# Sheet1.net
KiCad netlist of a schematic drawn in Altium Designer
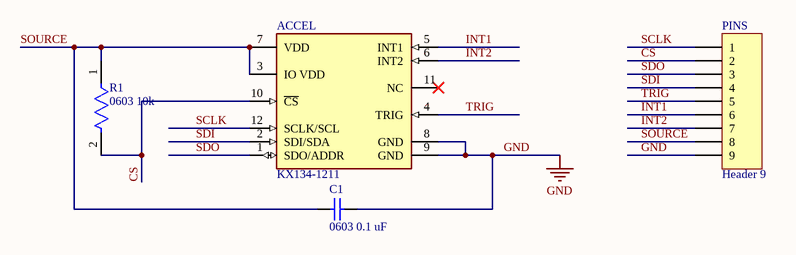
[diagram p0: Sheet1.SchDoc]

(export (version "E")
  (design (tool "Eeschema 10.0.6"))
  (components
    (comp (ref "ACCEL")
      (value "KX134-1211")
      (footprint "FP-KX134-1211-MFG")
      (description "105C OPERATING HIGHER BANDWIDTH,")
      (libsource (lib "Altium Content Vault") (part "690d2a4d51cffb5fe50aad75ddab18e"))
    )
    (comp (ref "C1")
      (value "0603 0.1 uF")
      (footprint "CAPC1608X95X40NL15T15")
      (fields (field (name "PART NUMBER") "VJ0603A101KXBCW1BC") (field (name "MANUFACTURER") "Vitramon"))
      (libsource (lib "Altium Content Vault") (part "CAP"))
    )
    (comp (ref "PINS")
      (value "Header 9")
      (footprint "HDR1X9")
      (description "Header, 9-Pin")
      (fields (field (name "PUBLISHER") "Altium Limited"))
      (libsource (lib "Miscellaneous Connectors") (part "Header 9"))
    )
    (comp (ref "R1")
      (value "0603 10k")
      (footprint "FP-CRCW0603-e3-IPC_C")
      (description "RES Thick Film, 100Ω, 5%, 0.1W, 200ppm/°C, 0603")
      (fields (field (name "TOLERANCE") "5%"))
      (libsource (lib "Altium Content Vault") (part "1029c3af85768c4190bb7ad29bc67b5"))
    )
  )
  (nets
    (net (code "1") (name "/CS") (class "Default")
      (node (ref "ACCEL") (pin "10") (pinfunction "~{CS}_10") (pintype "input"))
      (node (ref "PINS") (pin "2") (pinfunction "2_2") (pintype "passive"))
      (node (ref "R1") (pin "2") (pinfunction "2_2") (pintype "passive"))
    )
    (net (code "2") (name "/INT1") (class "Default")
      (node (ref "ACCEL") (pin "5") (pinfunction "INT1_5") (pintype "input"))
      (node (ref "PINS") (pin "6") (pinfunction "6_6") (pintype "passive"))
    )
    (net (code "3") (name "/INT2") (class "Default")
      (node (ref "ACCEL") (pin "6") (pinfunction "INT2_6") (pintype "input"))
      (node (ref "PINS") (pin "7") (pinfunction "7_7") (pintype "passive"))
    )
    (net (code "4") (name "/SCLK") (class "Default")
      (node (ref "ACCEL") (pin "12") (pinfunction "SCLK/SCL_12") (pintype "input"))
      (node (ref "PINS") (pin "1") (pinfunction "1_1") (pintype "passive"))
    )
    (net (code "5") (name "/SDI") (class "Default")
      (node (ref "ACCEL") (pin "2") (pinfunction "SDI/SDA_2") (pintype "input"))
      (node (ref "PINS") (pin "4") (pinfunction "4_4") (pintype "passive"))
    )
    (net (code "6") (name "/SDO") (class "Default")
      (node (ref "ACCEL") (pin "1") (pinfunction "SDO/ADDR_1") (pintype "bidirectional"))
      (node (ref "PINS") (pin "3") (pinfunction "3_3") (pintype "passive"))
    )
    (net (code "7") (name "/SOURCE") (class "Default")
      (node (ref "ACCEL") (pin "3") (pinfunction "IO_VDD_3") (pintype "power_in"))
      (node (ref "ACCEL") (pin "7") (pinfunction "VDD_7") (pintype "power_in"))
      (node (ref "C1") (pin "1") (pinfunction "1_1") (pintype "passive"))
      (node (ref "PINS") (pin "8") (pinfunction "8_8") (pintype "passive"))
      (node (ref "R1") (pin "1") (pinfunction "1_1") (pintype "passive"))
    )
    (net (code "8") (name "/TRIG") (class "Default")
      (node (ref "ACCEL") (pin "4") (pinfunction "TRIG_4") (pintype "input"))
      (node (ref "PINS") (pin "5") (pinfunction "5_5") (pintype "passive"))
    )
    (net (code "9") (name "GND") (class "Default")
      (node (ref "ACCEL") (pin "8") (pinfunction "GND_8") (pintype "power_in"))
      (node (ref "ACCEL") (pin "9") (pinfunction "GND_9") (pintype "power_in"))
      (node (ref "C1") (pin "2") (pinfunction "2_2") (pintype "passive"))
      (node (ref "PINS") (pin "9") (pinfunction "9_9") (pintype "passive"))
    )
    (net (code "10") (name "unconnected-(ACCEL-NC-Pad11)") (class "Default")
      (node (ref "ACCEL") (pin "11") (pinfunction "NC_11") (pintype "passive+no_connect"))
    )
  )
)
